# power_supply_board.net
KiCad netlist of a schematic drawn in EAGLE
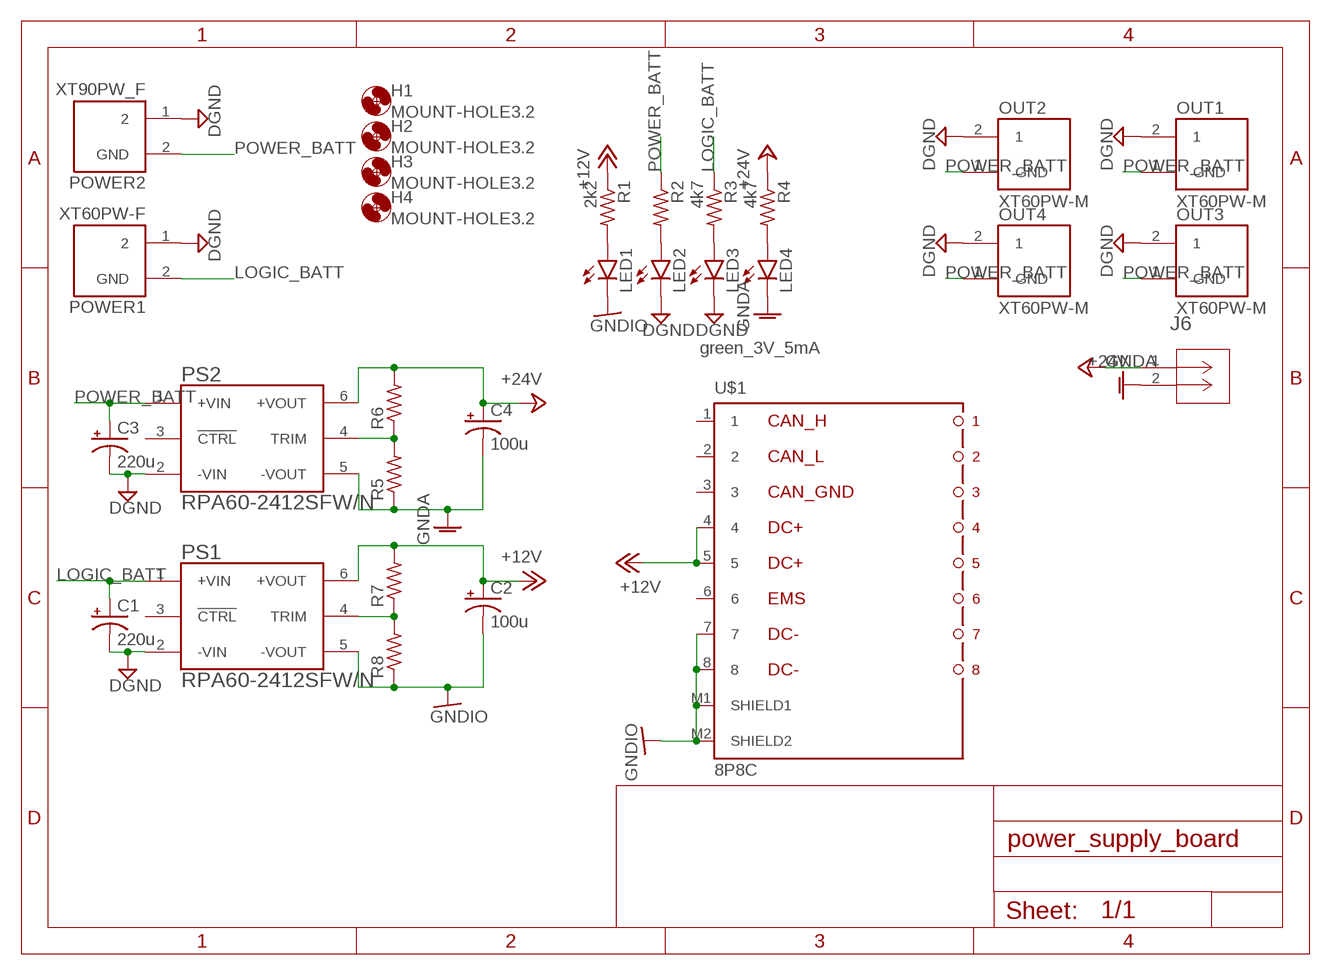
[diagram p0: schematic, sheet 1]

(export (version "E")
  (design (tool "Eeschema 10.0.6"))
  (components
    (comp (ref "C1")
      (value "220u")
      (footprint "eagle-import:E2,5-5")
      (libsource (lib "eagle-import") (part "CPOL-USE2.5-5"))
    )
    (comp (ref "C2")
      (value "100u")
      (footprint "eagle-import:E2-5")
      (libsource (lib "eagle-import") (part "CPOL-USE2-5"))
    )
    (comp (ref "C3")
      (value "220u")
      (footprint "eagle-import:E2,5-5")
      (libsource (lib "eagle-import") (part "CPOL-USE2.5-5"))
    )
    (comp (ref "C4")
      (value "100u")
      (footprint "eagle-import:E2-5")
      (libsource (lib "eagle-import") (part "CPOL-USE2-5"))
    )
    (comp (ref "H1")
      (value "MOUNT-HOLE3.2")
      (footprint "eagle-import:3,2")
      (libsource (lib "eagle-import") (part "MOUNT-HOLE3.2"))
    )
    (comp (ref "H2")
      (value "MOUNT-HOLE3.2")
      (footprint "eagle-import:3,2")
      (libsource (lib "eagle-import") (part "MOUNT-HOLE3.2"))
    )
    (comp (ref "H3")
      (value "MOUNT-HOLE3.2")
      (footprint "eagle-import:3,2")
      (libsource (lib "eagle-import") (part "MOUNT-HOLE3.2"))
    )
    (comp (ref "H4")
      (value "MOUNT-HOLE3.2")
      (footprint "eagle-import:3,2")
      (libsource (lib "eagle-import") (part "MOUNT-HOLE3.2"))
    )
    (comp (ref "J6")
      (value "1744426-2")
      (footprint "eagle-import:CONN2_1744426-2")
      (fields (field (name "MANUFACTURER_PART_NUMBER") "17444262"))
      (libsource (lib "eagle-import") (part "1744426-2"))
    )
    (comp (ref "LED1")
      (value "LEDSML0603")
      (footprint "eagle-import:SML0603")
      (libsource (lib "eagle-import") (part "LEDSML0603"))
    )
    (comp (ref "LED2")
      (value "LEDSML0603")
      (footprint "eagle-import:SML0603")
      (libsource (lib "eagle-import") (part "LEDSML0603"))
    )
    (comp (ref "LED3")
      (value "green_3V_5mA")
      (footprint "eagle-import:SML0603")
      (libsource (lib "eagle-import") (part "LEDSML0603"))
    )
    (comp (ref "LED4")
      (value "LEDSML0603")
      (footprint "eagle-import:SML0603")
      (libsource (lib "eagle-import") (part "LEDSML0603"))
    )
    (comp (ref "OUT1")
      (value "XT60PW-M")
      (footprint "eagle-import:AMASS_XT60PW_M")
      (libsource (lib "eagle-import") (part "XT60PW-M"))
    )
    (comp (ref "OUT2")
      (value "XT60PW-M")
      (footprint "eagle-import:AMASS_XT60PW_M")
      (libsource (lib "eagle-import") (part "XT60PW-M"))
    )
    (comp (ref "OUT3")
      (value "XT60PW-M")
      (footprint "eagle-import:AMASS_XT60PW_M")
      (libsource (lib "eagle-import") (part "XT60PW-M"))
    )
    (comp (ref "OUT4")
      (value "XT60PW-M")
      (footprint "eagle-import:AMASS_XT60PW_M")
      (libsource (lib "eagle-import") (part "XT60PW-M"))
    )
    (comp (ref "POWER1")
      (value "XT60PW-F")
      (footprint "eagle-import:AMASS_XT60PW-F")
      (fields (field (name "MF") "AMASS") (field (name "MP") "XT60PW-M "))
      (libsource (lib "eagle-import") (part "XT60PW-F"))
    )
    (comp (ref "POWER2")
      (value "XT90PW_F")
      (footprint "eagle-import:AMASS_XT90PW_F")
      (libsource (lib "eagle-import") (part "XT90PW_F"))
    )
    (comp (ref "PS1")
      (value "RPA60-2412SFW/N")
      (footprint "eagle-import:CONV_RPA60-2412SFW_N")
      (fields (field (name "MF") "Recom Power"))
      (libsource (lib "eagle-import") (part "RPA60-2412SFW/N"))
    )
    (comp (ref "PS2")
      (value "RPA60-2412SFW/N")
      (footprint "eagle-import:CONV_RPA60-2412SFW_N")
      (fields (field (name "MF") "Recom Power"))
      (libsource (lib "eagle-import") (part "RPA60-2412SFW/N"))
    )
    (comp (ref "R1")
      (value "2k2")
      (footprint "eagle-import:R0603")
      (libsource (lib "eagle-import") (part "R-US_R0603"))
    )
    (comp (ref "R2")
      (value "R-US_R0603")
      (footprint "eagle-import:R0603")
      (libsource (lib "eagle-import") (part "R-US_R0603"))
    )
    (comp (ref "R3")
      (value "4k7")
      (footprint "eagle-import:R0603")
      (libsource (lib "eagle-import") (part "R-US_R0603"))
    )
    (comp (ref "R4")
      (value "4k7")
      (footprint "eagle-import:R0603")
      (libsource (lib "eagle-import") (part "R-US_R0603"))
    )
    (comp (ref "R5")
      (value "R-US_R0603")
      (footprint "eagle-import:R0603")
      (libsource (lib "eagle-import") (part "R-US_R0603"))
    )
    (comp (ref "R6")
      (value "R-US_R0603")
      (footprint "eagle-import:R0603")
      (libsource (lib "eagle-import") (part "R-US_R0603"))
    )
    (comp (ref "R7")
      (value "R-US_R0603")
      (footprint "eagle-import:R0603")
      (libsource (lib "eagle-import") (part "R-US_R0603"))
    )
    (comp (ref "R8")
      (value "R-US_R0603")
      (footprint "eagle-import:R0603")
      (libsource (lib "eagle-import") (part "R-US_R0603"))
    )
    (comp (ref "U$1")
      (value "8P8C")
      (footprint "eagle-import:8P8C")
      (libsource (lib "eagle-import") (part "8P8C"))
    )
  )
  (nets
    (net (code "1") (name "+12V") (class "Default")
      (node (ref "C2") (pin "+") (pinfunction "+_+") (pintype "passive"))
      (node (ref "PS1") (pin "6") (pinfunction "+VOUT_6") (pintype "output"))
      (node (ref "R1") (pin "1") (pinfunction "1_1") (pintype "passive"))
      (node (ref "R7") (pin "2") (pinfunction "2_2") (pintype "passive"))
      (node (ref "U$1") (pin "4") (pinfunction "4_4") (pintype "input"))
      (node (ref "U$1") (pin "5") (pinfunction "5_5") (pintype "input"))
    )
    (net (code "2") (name "+24V") (class "Default")
      (node (ref "C4") (pin "+") (pinfunction "+_+") (pintype "passive"))
      (node (ref "J6") (pin "1") (pinfunction "1_1") (pintype "passive"))
      (node (ref "PS2") (pin "6") (pinfunction "+VOUT_6") (pintype "output"))
      (node (ref "R4") (pin "1") (pinfunction "1_1") (pintype "passive"))
      (node (ref "R6") (pin "2") (pinfunction "2_2") (pintype "passive"))
    )
    (net (code "3") (name "/LOGIC_BATT") (class "Default")
      (node (ref "C1") (pin "+") (pinfunction "+_+") (pintype "passive"))
      (node (ref "POWER1") (pin "2") (pinfunction "GND_2") (pintype "passive"))
      (node (ref "PS1") (pin "1") (pinfunction "+VIN_1") (pintype "input"))
      (node (ref "R3") (pin "1") (pinfunction "1_1") (pintype "passive"))
    )
    (net (code "4") (name "/POWER_BATT") (class "Default")
      (node (ref "C3") (pin "+") (pinfunction "+_+") (pintype "passive"))
      (node (ref "OUT1") (pin "1") (pinfunction "GND_1") (pintype "passive"))
      (node (ref "OUT2") (pin "1") (pinfunction "GND_1") (pintype "passive"))
      (node (ref "OUT3") (pin "1") (pinfunction "GND_1") (pintype "passive"))
      (node (ref "OUT4") (pin "1") (pinfunction "GND_1") (pintype "passive"))
      (node (ref "POWER2") (pin "2") (pinfunction "GND_2") (pintype "passive"))
      (node (ref "PS2") (pin "1") (pinfunction "+VIN_1") (pintype "input"))
      (node (ref "R2") (pin "1") (pinfunction "1_1") (pintype "passive"))
    )
    (net (code "5") (name "DGND") (class "Default")
      (node (ref "C1") (pin "-") (pinfunction "-_-") (pintype "passive"))
      (node (ref "C3") (pin "-") (pinfunction "-_-") (pintype "passive"))
      (node (ref "LED2") (pin "C") (pinfunction "C_C") (pintype "passive"))
      (node (ref "LED3") (pin "C") (pinfunction "C_C") (pintype "passive"))
      (node (ref "OUT1") (pin "2") (pinfunction "1_2") (pintype "passive"))
      (node (ref "OUT2") (pin "2") (pinfunction "1_2") (pintype "passive"))
      (node (ref "OUT3") (pin "2") (pinfunction "1_2") (pintype "passive"))
      (node (ref "OUT4") (pin "2") (pinfunction "1_2") (pintype "passive"))
      (node (ref "POWER1") (pin "1") (pinfunction "2_1") (pintype "passive"))
      (node (ref "POWER2") (pin "1") (pinfunction "2_1") (pintype "passive"))
      (node (ref "PS1") (pin "2") (pinfunction "-VIN_2") (pintype "input"))
      (node (ref "PS2") (pin "2") (pinfunction "-VIN_2") (pintype "input"))
    )
    (net (code "6") (name "GNDA") (class "Default")
      (node (ref "C4") (pin "-") (pinfunction "-_-") (pintype "passive"))
      (node (ref "J6") (pin "2") (pinfunction "2_2") (pintype "passive"))
      (node (ref "LED4") (pin "C") (pinfunction "C_C") (pintype "passive"))
      (node (ref "PS2") (pin "5") (pinfunction "-VOUT_5") (pintype "output"))
      (node (ref "R5") (pin "1") (pinfunction "1_1") (pintype "passive"))
    )
    (net (code "7") (name "GNDIO") (class "Default")
      (node (ref "C2") (pin "-") (pinfunction "-_-") (pintype "passive"))
      (node (ref "LED1") (pin "C") (pinfunction "C_C") (pintype "passive"))
      (node (ref "PS1") (pin "5") (pinfunction "-VOUT_5") (pintype "output"))
      (node (ref "R8") (pin "1") (pinfunction "1_1") (pintype "passive"))
      (node (ref "U$1") (pin "7") (pinfunction "7_7") (pintype "input"))
      (node (ref "U$1") (pin "8") (pinfunction "8_8") (pintype "input"))
      (node (ref "U$1") (pin "M1") (pinfunction "SHIELD1_M1") (pintype "passive"))
      (node (ref "U$1") (pin "M2") (pinfunction "SHIELD2_M2") (pintype "passive"))
    )
    (net (code "8") (name "Net-(LED1-PadA)") (class "Default")
      (node (ref "LED1") (pin "A") (pinfunction "A_A") (pintype "passive"))
      (node (ref "R1") (pin "2") (pinfunction "2_2") (pintype "passive"))
    )
    (net (code "9") (name "Net-(LED2-PadA)") (class "Default")
      (node (ref "LED2") (pin "A") (pinfunction "A_A") (pintype "passive"))
      (node (ref "R2") (pin "2") (pinfunction "2_2") (pintype "passive"))
    )
    (net (code "10") (name "Net-(LED3-PadA)") (class "Default")
      (node (ref "LED3") (pin "A") (pinfunction "A_A") (pintype "passive"))
      (node (ref "R3") (pin "2") (pinfunction "2_2") (pintype "passive"))
    )
    (net (code "11") (name "Net-(LED4-PadA)") (class "Default")
      (node (ref "LED4") (pin "A") (pinfunction "A_A") (pintype "passive"))
      (node (ref "R4") (pin "2") (pinfunction "2_2") (pintype "passive"))
    )
    (net (code "12") (name "Net-(PS1-TRIM)") (class "Default")
      (node (ref "PS1") (pin "4") (pinfunction "TRIM_4") (pintype "passive"))
      (node (ref "R7") (pin "1") (pinfunction "1_1") (pintype "passive"))
      (node (ref "R8") (pin "2") (pinfunction "2_2") (pintype "passive"))
    )
    (net (code "13") (name "Net-(PS2-TRIM)") (class "Default")
      (node (ref "PS2") (pin "4") (pinfunction "TRIM_4") (pintype "passive"))
      (node (ref "R5") (pin "2") (pinfunction "2_2") (pintype "passive"))
      (node (ref "R6") (pin "1") (pinfunction "1_1") (pintype "passive"))
    )
    (net (code "14") (name "unconnected-(PS1-~{CTRL}-Pad3)") (class "Default")
      (node (ref "PS1") (pin "3") (pinfunction "~{CTRL}_3") (pintype "input"))
    )
    (net (code "15") (name "unconnected-(PS2-~{CTRL}-Pad3)") (class "Default")
      (node (ref "PS2") (pin "3") (pinfunction "~{CTRL}_3") (pintype "input"))
    )
    (net (code "16") (name "unconnected-(U$1-Pad1)") (class "Default")
      (node (ref "U$1") (pin "1") (pinfunction "1_1") (pintype "input"))
    )
    (net (code "17") (name "unconnected-(U$1-Pad2)") (class "Default")
      (node (ref "U$1") (pin "2") (pinfunction "2_2") (pintype "input"))
    )
    (net (code "18") (name "unconnected-(U$1-Pad3)") (class "Default")
      (node (ref "U$1") (pin "3") (pinfunction "3_3") (pintype "input"))
    )
    (net (code "19") (name "unconnected-(U$1-Pad6)") (class "Default")
      (node (ref "U$1") (pin "6") (pinfunction "6_6") (pintype "input"))
    )
  )
)
